# infnoise_goldfingers.net
KiCad netlist of a schematic drawn in EAGLE
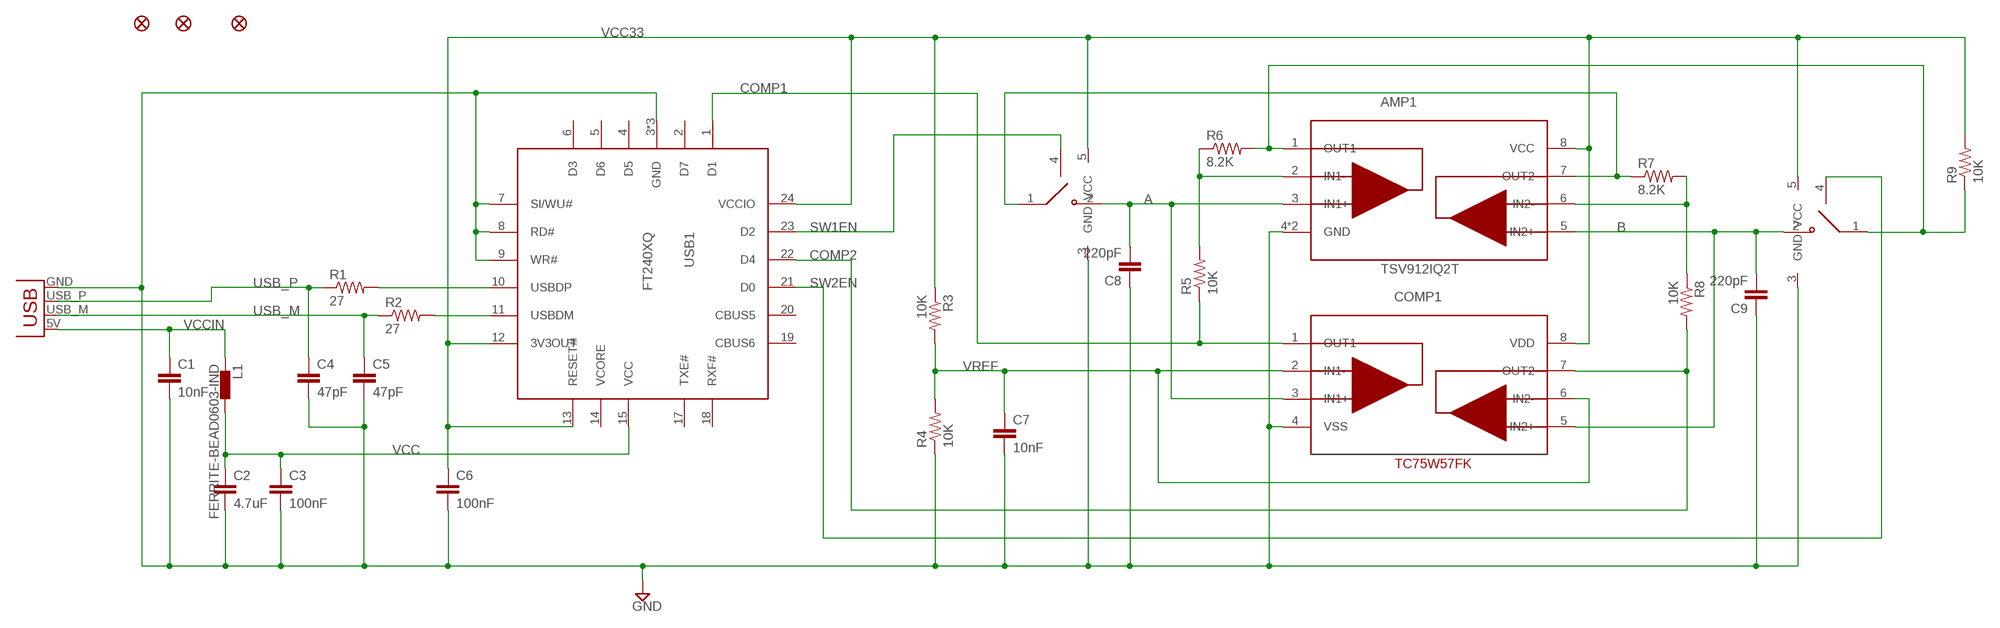
[diagram p0: schematic, sheet 1]

(export (version "E")
  (design (tool "Eeschema 10.0.6"))
  (components
    (comp (ref "AMP1")
      (value "TSV912IQ2T")
      (footprint "eagle-import:DFN8-2X3")
      (libsource (lib "eagle-import") (part "TSV912IQ2T"))
    )
    (comp (ref "C1")
      (value "10nF")
      (footprint "eagle-import:0603-CAP")
      (libsource (lib "eagle-import") (part "CAP0603-CAP"))
    )
    (comp (ref "C2")
      (value "4.7uF")
      (footprint "eagle-import:0603-CAP")
      (libsource (lib "eagle-import") (part "CAP0603-CAP"))
    )
    (comp (ref "C3")
      (value "100nF")
      (footprint "eagle-import:0603-CAP")
      (libsource (lib "eagle-import") (part "CAP0603-CAP"))
    )
    (comp (ref "C4")
      (value "47pF")
      (footprint "eagle-import:0603-CAP")
      (libsource (lib "eagle-import") (part "CAP0603-CAP"))
    )
    (comp (ref "C5")
      (value "47pF")
      (footprint "eagle-import:0603-CAP")
      (libsource (lib "eagle-import") (part "CAP0603-CAP"))
    )
    (comp (ref "C6")
      (value "100nF")
      (footprint "eagle-import:0603-CAP")
      (libsource (lib "eagle-import") (part "CAP0603-CAP"))
    )
    (comp (ref "C7")
      (value "10nF")
      (footprint "eagle-import:0603-CAP")
      (libsource (lib "eagle-import") (part "CAP0603-CAP"))
    )
    (comp (ref "C8")
      (value "220pF")
      (footprint "eagle-import:0603-CAP")
      (libsource (lib "eagle-import") (part "CAP0603-CAP"))
    )
    (comp (ref "C9")
      (value "220pF")
      (footprint "eagle-import:0603-CAP")
      (libsource (lib "eagle-import") (part "CAP0603-CAP"))
    )
    (comp (ref "COMP1")
      (value "TC75W57FK")
      (footprint "eagle-import:SSOP8-P-0.50A")
      (libsource (lib "eagle-import") (part "TC75W57FK"))
    )
    (comp (ref "FID1")
      (value "FIDUCIALUFIDUCIAL")
      (footprint "eagle-import:MICRO-FIDUCIAL")
      (libsource (lib "eagle-import") (part "FIDUCIALUFIDUCIAL"))
    )
    (comp (ref "FID2")
      (value "FIDUCIALUFIDUCIAL")
      (footprint "eagle-import:MICRO-FIDUCIAL")
      (libsource (lib "eagle-import") (part "FIDUCIALUFIDUCIAL"))
    )
    (comp (ref "FID3")
      (value "FIDUCIALUFIDUCIAL")
      (footprint "eagle-import:MICRO-FIDUCIAL")
      (libsource (lib "eagle-import") (part "FIDUCIALUFIDUCIAL"))
    )
    (comp (ref "L1")
      (value "FERRITE-BEAD0603-IND")
      (footprint "eagle-import:0603-IND")
      (libsource (lib "eagle-import") (part "FERRITE-BEAD0603-IND"))
    )
    (comp (ref "R1")
      (value "27")
      (footprint "eagle-import:0603-RES")
      (libsource (lib "eagle-import") (part "RESISTOR0603-RES"))
    )
    (comp (ref "R2")
      (value "27")
      (footprint "eagle-import:0603-RES")
      (libsource (lib "eagle-import") (part "RESISTOR0603-RES"))
    )
    (comp (ref "R3")
      (value "10K")
      (footprint "eagle-import:0603-RES")
      (libsource (lib "eagle-import") (part "RESISTOR0603-RES"))
    )
    (comp (ref "R4")
      (value "10K")
      (footprint "eagle-import:0603-RES")
      (libsource (lib "eagle-import") (part "RESISTOR0603-RES"))
    )
    (comp (ref "R5")
      (value "10K")
      (footprint "eagle-import:0603-RES")
      (libsource (lib "eagle-import") (part "RESISTOR0603-RES"))
    )
    (comp (ref "R6")
      (value "8.2K")
      (footprint "eagle-import:0603-RES")
      (libsource (lib "eagle-import") (part "RESISTOR0603-RES"))
    )
    (comp (ref "R7")
      (value "8.2K")
      (footprint "eagle-import:0603-RES")
      (libsource (lib "eagle-import") (part "RESISTOR0603-RES"))
    )
    (comp (ref "R8")
      (value "10K")
      (footprint "eagle-import:0603-RES")
      (libsource (lib "eagle-import") (part "RESISTOR0603-RES"))
    )
    (comp (ref "R9")
      (value "10K")
      (footprint "eagle-import:0603-RES")
      (libsource (lib "eagle-import") (part "RESISTOR0603-RES"))
    )
    (comp (ref "SW1")
      (value "MC74VHC1G66DFT1G")
      (footprint "eagle-import:SC70-5L")
      (libsource (lib "eagle-import") (part "MC74VHC1G66DFT1G"))
    )
    (comp (ref "SW2")
      (value "MC74VHC1G66DFT1G")
      (footprint "eagle-import:SC70-5L")
      (libsource (lib "eagle-import") (part "MC74VHC1G66DFT1G"))
    )
    (comp (ref "USB1")
      (value "FT240XQ")
      (footprint "eagle-import:QFN24-4X4")
      (libsource (lib "eagle-import") (part "FT240XQ"))
    )
    (comp (ref "X1")
      (value "USBRAWPINS")
      (footprint "eagle-import:USB-A-RAWPINS")
      (libsource (lib "eagle-import") (part "USBRAWPINS"))
    )
  )
  (nets
    (net (code "1") (name "/A") (class "Default")
      (node (ref "AMP1") (pin "3") (pinfunction "IN1+_3") (pintype "bidirectional"))
      (node (ref "C8") (pin "2") (pinfunction "2_2") (pintype "passive"))
      (node (ref "COMP1") (pin "3") (pinfunction "IN1+_3") (pintype "bidirectional"))
      (node (ref "SW1") (pin "2") (pinfunction "NO_2") (pintype "bidirectional"))
    )
    (net (code "2") (name "/B") (class "Default")
      (node (ref "AMP1") (pin "5") (pinfunction "IN2+_5") (pintype "bidirectional"))
      (node (ref "C9") (pin "2") (pinfunction "2_2") (pintype "passive"))
      (node (ref "COMP1") (pin "5") (pinfunction "IN2+_5") (pintype "bidirectional"))
      (node (ref "SW2") (pin "2") (pinfunction "NO_2") (pintype "bidirectional"))
    )
    (net (code "3") (name "/COMP1") (class "Default")
      (node (ref "COMP1") (pin "1") (pinfunction "OUT1_1") (pintype "bidirectional"))
      (node (ref "R5") (pin "1") (pinfunction "1_1") (pintype "passive"))
      (node (ref "USB1") (pin "1") (pinfunction "D1_1") (pintype "bidirectional"))
    )
    (net (code "4") (name "/COMP2") (class "Default")
      (node (ref "COMP1") (pin "7") (pinfunction "OUT2_7") (pintype "bidirectional"))
      (node (ref "R8") (pin "2") (pinfunction "2_2") (pintype "passive"))
      (node (ref "USB1") (pin "22") (pinfunction "D4_22") (pintype "bidirectional"))
    )
    (net (code "5") (name "/SW1EN") (class "Default")
      (node (ref "SW1") (pin "4") (pinfunction "IN_4") (pintype "bidirectional"))
      (node (ref "USB1") (pin "23") (pinfunction "D2_23") (pintype "bidirectional"))
    )
    (net (code "6") (name "/SW2EN") (class "Default")
      (node (ref "SW2") (pin "4") (pinfunction "IN_4") (pintype "bidirectional"))
      (node (ref "USB1") (pin "21") (pinfunction "D0_21") (pintype "bidirectional"))
    )
    (net (code "7") (name "/USB_M") (class "Default")
      (node (ref "C5") (pin "1") (pinfunction "1_1") (pintype "passive"))
      (node (ref "R2") (pin "1") (pinfunction "1_1") (pintype "passive"))
      (node (ref "X1") (pin "USB_M") (pinfunction "D-_USB_M") (pintype "bidirectional"))
    )
    (net (code "8") (name "/USB_P") (class "Default")
      (node (ref "C4") (pin "1") (pinfunction "1_1") (pintype "passive"))
      (node (ref "R1") (pin "1") (pinfunction "1_1") (pintype "passive"))
      (node (ref "X1") (pin "USB_P") (pinfunction "D+_USB_P") (pintype "bidirectional"))
    )
    (net (code "9") (name "/VCC") (class "Default")
      (node (ref "C2") (pin "1") (pinfunction "1_1") (pintype "passive"))
      (node (ref "C3") (pin "1") (pinfunction "1_1") (pintype "passive"))
      (node (ref "L1") (pin "2") (pinfunction "2_2") (pintype "passive"))
      (node (ref "USB1") (pin "15") (pinfunction "VCC_15") (pintype "bidirectional"))
    )
    (net (code "10") (name "/VCC33") (class "Default")
      (node (ref "AMP1") (pin "8") (pinfunction "VCC_8") (pintype "bidirectional"))
      (node (ref "C6") (pin "1") (pinfunction "1_1") (pintype "passive"))
      (node (ref "COMP1") (pin "8") (pinfunction "VDD_8") (pintype "bidirectional"))
      (node (ref "R3") (pin "1") (pinfunction "1_1") (pintype "passive"))
      (node (ref "R9") (pin "2") (pinfunction "2_2") (pintype "passive"))
      (node (ref "SW1") (pin "5") (pinfunction "VCC_5") (pintype "bidirectional"))
      (node (ref "SW2") (pin "5") (pinfunction "VCC_5") (pintype "bidirectional"))
      (node (ref "USB1") (pin "12") (pinfunction "3V3OUT_12") (pintype "bidirectional"))
      (node (ref "USB1") (pin "13") (pinfunction "RESET#_13") (pintype "bidirectional"))
      (node (ref "USB1") (pin "24") (pinfunction "VCCIO_24") (pintype "bidirectional"))
    )
    (net (code "11") (name "/VCCIN") (class "Default")
      (node (ref "C1") (pin "1") (pinfunction "1_1") (pintype "passive"))
      (node (ref "L1") (pin "1") (pinfunction "1_1") (pintype "passive"))
      (node (ref "X1") (pin "5V") (pinfunction "VCC_5V") (pintype "bidirectional"))
    )
    (net (code "12") (name "/VREF") (class "Default")
      (node (ref "C7") (pin "1") (pinfunction "1_1") (pintype "passive"))
      (node (ref "COMP1") (pin "2") (pinfunction "IN1-_2") (pintype "bidirectional"))
      (node (ref "COMP1") (pin "6") (pinfunction "IN2-_6") (pintype "bidirectional"))
      (node (ref "R3") (pin "2") (pinfunction "2_2") (pintype "passive"))
      (node (ref "R4") (pin "2") (pinfunction "2_2") (pintype "passive"))
    )
    (net (code "13") (name "GND") (class "Default")
      (node (ref "AMP1") (pin "4") (pinfunction "GND_4") (pintype "bidirectional"))
      (node (ref "AMP1") (pin "EXP") (pinfunction "GND_EXP") (pintype "bidirectional"))
      (node (ref "C1") (pin "2") (pinfunction "2_2") (pintype "passive"))
      (node (ref "C2") (pin "2") (pinfunction "2_2") (pintype "passive"))
      (node (ref "C3") (pin "2") (pinfunction "2_2") (pintype "passive"))
      (node (ref "C4") (pin "2") (pinfunction "2_2") (pintype "passive"))
      (node (ref "C5") (pin "2") (pinfunction "2_2") (pintype "passive"))
      (node (ref "C6") (pin "2") (pinfunction "2_2") (pintype "passive"))
      (node (ref "C7") (pin "2") (pinfunction "2_2") (pintype "passive"))
      (node (ref "C8") (pin "1") (pinfunction "1_1") (pintype "passive"))
      (node (ref "C9") (pin "1") (pinfunction "1_1") (pintype "passive"))
      (node (ref "COMP1") (pin "4") (pinfunction "VSS_4") (pintype "bidirectional"))
      (node (ref "R4") (pin "1") (pinfunction "1_1") (pintype "passive"))
      (node (ref "SW1") (pin "3") (pinfunction "GND_3") (pintype "bidirectional"))
      (node (ref "SW2") (pin "3") (pinfunction "GND_3") (pintype "bidirectional"))
      (node (ref "USB1") (pin "16") (pinfunction "GND_16") (pintype "bidirectional"))
      (node (ref "USB1") (pin "3") (pinfunction "GND_3") (pintype "bidirectional"))
      (node (ref "USB1") (pin "7") (pinfunction "SI/WU#_7") (pintype "bidirectional"))
      (node (ref "USB1") (pin "8") (pinfunction "RD#_8") (pintype "bidirectional"))
      (node (ref "USB1") (pin "9") (pinfunction "WR#_9") (pintype "bidirectional"))
      (node (ref "USB1") (pin "EXP") (pinfunction "GND_EXP") (pintype "bidirectional"))
      (node (ref "X1") (pin "GND") (pinfunction "GND_GND") (pintype "bidirectional"))
    )
    (net (code "14") (name "Net-(AMP1-IN1-)") (class "Default")
      (node (ref "AMP1") (pin "2") (pinfunction "IN1-_2") (pintype "bidirectional"))
      (node (ref "R5") (pin "2") (pinfunction "2_2") (pintype "passive"))
      (node (ref "R6") (pin "1") (pinfunction "1_1") (pintype "passive"))
    )
    (net (code "15") (name "Net-(AMP1-IN2-)") (class "Default")
      (node (ref "AMP1") (pin "6") (pinfunction "IN2-_6") (pintype "bidirectional"))
      (node (ref "R7") (pin "2") (pinfunction "2_2") (pintype "passive"))
      (node (ref "R8") (pin "1") (pinfunction "1_1") (pintype "passive"))
    )
    (net (code "16") (name "Net-(AMP1-OUT1)") (class "Default")
      (node (ref "AMP1") (pin "1") (pinfunction "OUT1_1") (pintype "bidirectional"))
      (node (ref "R6") (pin "2") (pinfunction "2_2") (pintype "passive"))
      (node (ref "R9") (pin "1") (pinfunction "1_1") (pintype "passive"))
      (node (ref "SW2") (pin "1") (pinfunction "COM_1") (pintype "bidirectional"))
    )
    (net (code "17") (name "Net-(AMP1-OUT2)") (class "Default")
      (node (ref "AMP1") (pin "7") (pinfunction "OUT2_7") (pintype "bidirectional"))
      (node (ref "R7") (pin "1") (pinfunction "1_1") (pintype "passive"))
      (node (ref "SW1") (pin "1") (pinfunction "COM_1") (pintype "bidirectional"))
    )
    (net (code "18") (name "Net-(USB1-USBDM)") (class "Default")
      (node (ref "R2") (pin "2") (pinfunction "2_2") (pintype "passive"))
      (node (ref "USB1") (pin "11") (pinfunction "USBDM_11") (pintype "bidirectional"))
    )
    (net (code "19") (name "Net-(USB1-USBDP)") (class "Default")
      (node (ref "R1") (pin "2") (pinfunction "2_2") (pintype "passive"))
      (node (ref "USB1") (pin "10") (pinfunction "USBDP_10") (pintype "bidirectional"))
    )
    (net (code "20") (name "unconnected-(USB1-CBUS5-Pad20)") (class "Default")
      (node (ref "USB1") (pin "20") (pinfunction "CBUS5_20") (pintype "bidirectional"))
    )
    (net (code "21") (name "unconnected-(USB1-CBUS6-Pad19)") (class "Default")
      (node (ref "USB1") (pin "19") (pinfunction "CBUS6_19") (pintype "bidirectional"))
    )
    (net (code "22") (name "unconnected-(USB1-D3-Pad6)") (class "Default")
      (node (ref "USB1") (pin "6") (pinfunction "D3_6") (pintype "bidirectional"))
    )
    (net (code "23") (name "unconnected-(USB1-D5-Pad4)") (class "Default")
      (node (ref "USB1") (pin "4") (pinfunction "D5_4") (pintype "bidirectional"))
    )
    (net (code "24") (name "unconnected-(USB1-D6-Pad5)") (class "Default")
      (node (ref "USB1") (pin "5") (pinfunction "D6_5") (pintype "bidirectional"))
    )
    (net (code "25") (name "unconnected-(USB1-D7-Pad2)") (class "Default")
      (node (ref "USB1") (pin "2") (pinfunction "D7_2") (pintype "bidirectional"))
    )
    (net (code "26") (name "unconnected-(USB1-RXF#-Pad18)") (class "Default")
      (node (ref "USB1") (pin "18") (pinfunction "RXF#_18") (pintype "bidirectional"))
    )
    (net (code "27") (name "unconnected-(USB1-TXE#-Pad17)") (class "Default")
      (node (ref "USB1") (pin "17") (pinfunction "TXE#_17") (pintype "bidirectional"))
    )
    (net (code "28") (name "unconnected-(USB1-VCORE-Pad14)") (class "Default")
      (node (ref "USB1") (pin "14") (pinfunction "VCORE_14") (pintype "bidirectional"))
    )
  )
)
